# Computation.net
KiCad netlist of a schematic drawn in Altium Designer
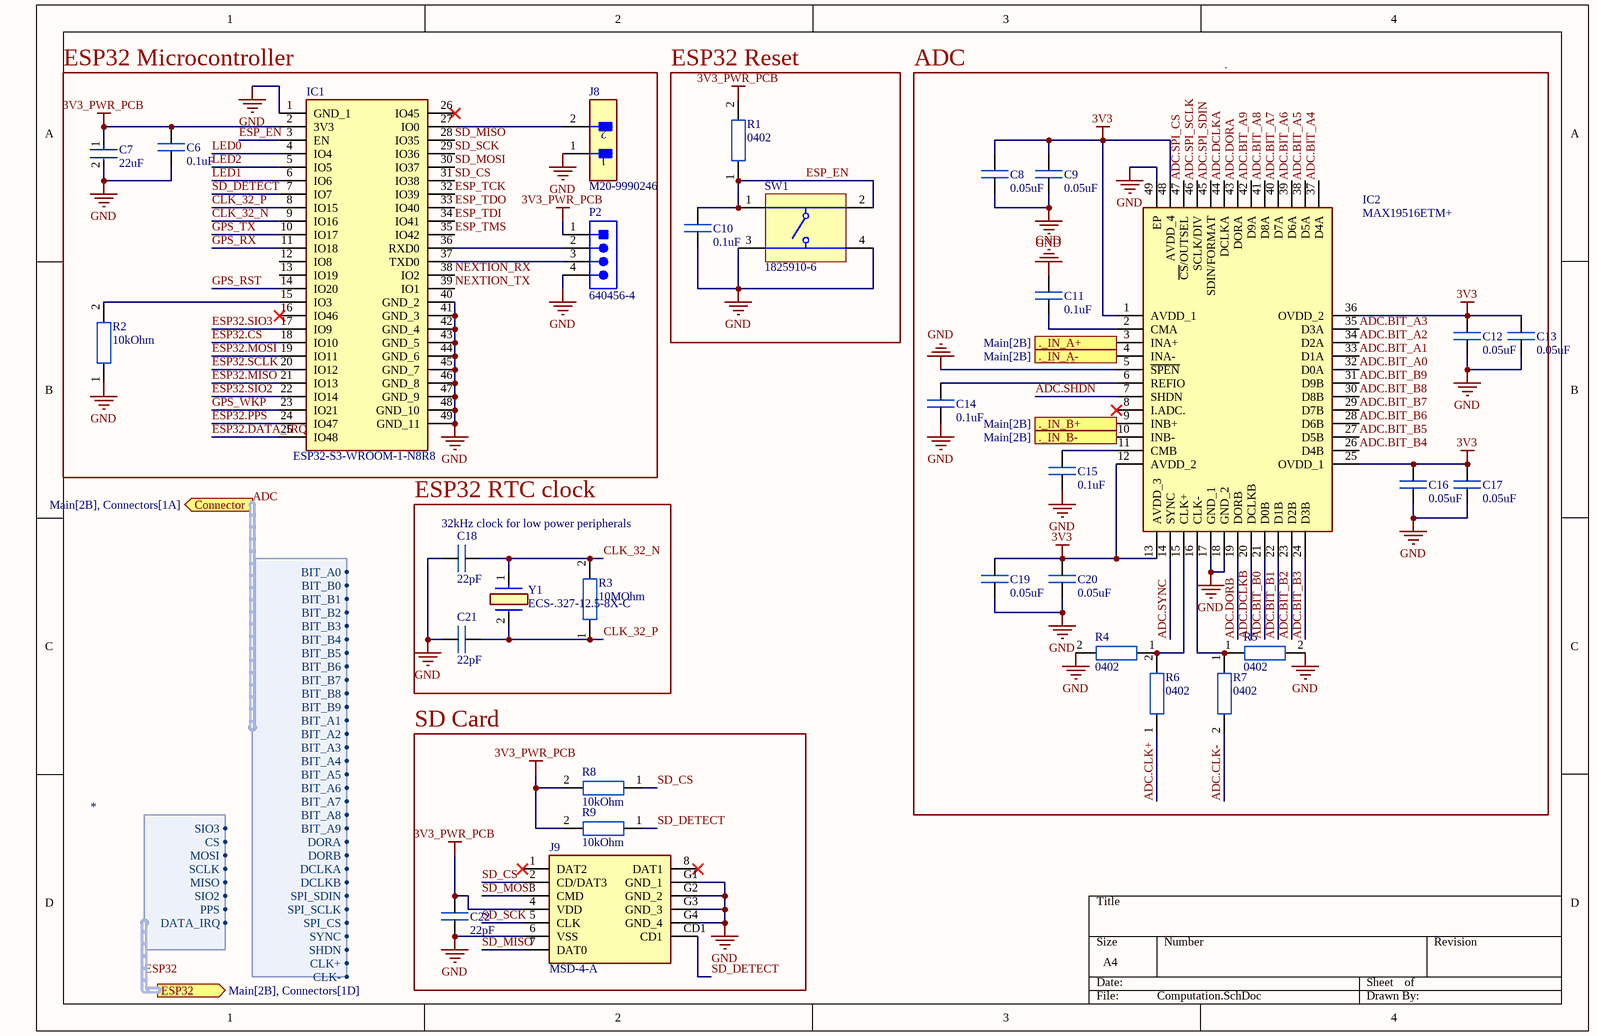
[diagram p0: Computation.SchDoc]

(export (version "E")
  (design (tool "Eeschema 10.0.6"))
  (components
    (comp (ref "C6")
      (value "0.1uF")
      (footprint "0402_footprint")
      (description "0402 capacitor")
      (libsource (lib "Schlib1") (part "Capacitor_0402"))
    )
    (comp (ref "C7")
      (value "22uF")
      (footprint "FP-CL21-IPC_B")
      (description "CL21 Series 0805 22uF 6.3V ±20% Tolerance X5R Multilayer Ceramic Chip Capacitor")
      (fields (field (name "TOLERANCE") "20%"))
      (libsource (lib "Altium Content Vault") (part "b4654b650e69147ec39a6b967a45e02"))
    )
    (comp (ref "C8")
      (value "0.05uF")
      (footprint "0402_footprint")
      (description "0402 capacitor")
      (libsource (lib "Schlib1") (part "Capacitor_0402"))
    )
    (comp (ref "C9")
      (value "0.05uF")
      (footprint "0402_footprint")
      (description "0402 capacitor")
      (libsource (lib "Schlib1") (part "Capacitor_0402"))
    )
    (comp (ref "C10")
      (value "0.1uF")
      (footprint "0402_footprint")
      (description "0402 capacitor")
      (libsource (lib "Schlib1") (part "Capacitor_0402"))
    )
    (comp (ref "C11")
      (value "0.1uF")
      (footprint "0402_footprint")
      (description "0402 capacitor")
      (libsource (lib "Schlib1") (part "Capacitor_0402"))
    )
    (comp (ref "C12")
      (value "0.05uF")
      (footprint "0402_footprint")
      (description "0402 capacitor")
      (libsource (lib "Schlib1") (part "Capacitor_0402"))
    )
    (comp (ref "C13")
      (value "0.05uF")
      (footprint "0402_footprint")
      (description "0402 capacitor")
      (libsource (lib "Schlib1") (part "Capacitor_0402"))
    )
    (comp (ref "C14")
      (value "0.1uF")
      (footprint "0402_footprint")
      (description "0402 capacitor")
      (libsource (lib "Schlib1") (part "Capacitor_0402"))
    )
    (comp (ref "C15")
      (value "0.1uF")
      (footprint "0402_footprint")
      (description "0402 capacitor")
      (libsource (lib "Schlib1") (part "Capacitor_0402"))
    )
    (comp (ref "C16")
      (value "0.05uF")
      (footprint "0402_footprint")
      (description "0402 capacitor")
      (libsource (lib "Schlib1") (part "Capacitor_0402"))
    )
    (comp (ref "C17")
      (value "0.05uF")
      (footprint "0402_footprint")
      (description "0402 capacitor")
      (libsource (lib "Schlib1") (part "Capacitor_0402"))
    )
    (comp (ref "C18")
      (value "22pF")
      (footprint "0402_footprint")
      (description "0402 capacitor")
      (libsource (lib "Schlib1") (part "Capacitor_0402"))
    )
    (comp (ref "C19")
      (value "0.05uF")
      (footprint "0402_footprint")
      (description "0402 capacitor")
      (libsource (lib "Schlib1") (part "Capacitor_0402"))
    )
    (comp (ref "C20")
      (value "0.05uF")
      (footprint "0402_footprint")
      (description "0402 capacitor")
      (libsource (lib "Schlib1") (part "Capacitor_0402"))
    )
    (comp (ref "C21")
      (value "22pF")
      (footprint "0402_footprint")
      (description "0402 capacitor")
      (libsource (lib "Schlib1") (part "Capacitor_0402"))
    )
    (comp (ref "C22")
      (value "22pF")
      (footprint "0402_footprint")
      (description "0402 capacitor")
      (libsource (lib "Schlib1") (part "Capacitor_0402"))
    )
    (comp (ref "IC1")
      (value "ESP32-S3-WROOM-1-N8R8")
      (footprint "SamacSys:ESP32S3WROOM1N8R8")
      (description "Integrated Circuit")
      (fields (field (name "MOUSER PART NUMBER") "356-EP32S3WROOM1N8R8"))
      (libsource (lib "*") (part "ESP32-S3-WROOM-1-N8R8"))
    )
    (comp (ref "IC2")
      (value "MAX19516ETM+")
      (footprint "SamacSys:QFN50P700X700X80-49N")
      (description "Integrated Circuit")
      (fields (field (name "MOUSER PART NUMBER") "700-MAX19516ETM"))
      (libsource (lib "*") (part "MAX19516ETM+"))
    )
    (comp (ref "J8")
      (value "M20-9990246")
      (footprint "FP-M20-9990246-MFG")
      (description "CONN HEADER VERT 2POS 2.54MM")
      (fields
        (field (name "OCTOPART") "https://octopart.com/m20-9990246-harwin-2590635")
        (field (name "MANUFACTURER") "Harwin")
      )
      (libsource (lib "Altium Content Vault") (part "3bc925449376181038e59eaffc5286c"))
    )
    (comp (ref "J9")
      (value "MSD-4-A")
      (footprint "SamacSys:MSD4A")
      (description "Connector")
      (libsource (lib "*") (part "MSD-4-A"))
    )
    (comp (ref "P2")
      (value "640456-4")
      (footprint "TECO-640456-4")
      (description "Male Header, Pitch 2.54 mm, 1 x 4 Position, Height 10.03 mm, Tail Length 3.56 mm, RoHS, Bulk")
      (fields (field (name "MANUFACTURER") "TE Connectivity"))
      (libsource (lib "Altium Content Vault") (part "CN-1P-M-R4"))
    )
    (comp (ref "R1")
      (value "0402")
      (footprint "0402_footprint")
      (description "0402 resistor")
      (libsource (lib "Schlib1") (part "Resistor_0402"))
    )
    (comp (ref "R2")
      (value "10kOhm")
      (footprint "0402_footprint")
      (description "0402 resistor")
      (libsource (lib "Schlib1") (part "Resistor_0402"))
    )
    (comp (ref "R3")
      (value "10MOhm")
      (footprint "0402_footprint")
      (description "0402 resistor")
      (libsource (lib "Schlib1") (part "Resistor_0402"))
    )
    (comp (ref "R4")
      (value "0402")
      (footprint "0402_footprint")
      (description "0402 resistor")
      (libsource (lib "Schlib1") (part "Resistor_0402"))
    )
    (comp (ref "R5")
      (value "0402")
      (footprint "0402_footprint")
      (description "0402 resistor")
      (libsource (lib "Schlib1") (part "Resistor_0402"))
    )
    (comp (ref "R6")
      (value "0402")
      (footprint "0402_footprint")
      (description "0402 resistor")
      (libsource (lib "Schlib1") (part "Resistor_0402"))
    )
    (comp (ref "R7")
      (value "0402")
      (footprint "0402_footprint")
      (description "0402 resistor")
      (libsource (lib "Schlib1") (part "Resistor_0402"))
    )
    (comp (ref "R8")
      (value "10kOhm")
      (footprint "0402_footprint")
      (description "0402 resistor")
      (libsource (lib "Schlib1") (part "Resistor_0402"))
    )
    (comp (ref "R9")
      (value "10kOhm")
      (footprint "0402_footprint")
      (description "0402 resistor")
      (libsource (lib "Schlib1") (part "Resistor_0402"))
    )
    (comp (ref "SW1")
      (value "1825910-6")
      (footprint "TECO-1825910-6_V")
      (description "Tact Switch, SPST-NO, 0.05 A, -35 to 85 degC, 4-Pin THD, RoHS, Bulk")
      (fields (field (name "MANUFACTURER") "TE Connectivity"))
      (libsource (lib "Altium Content Vault") (part "SW-SPST-4_A"))
    )
    (comp (ref "Y1")
      (value "ECS-.327-12.5-8X-C")
      (footprint "SamacSys:ECS3271258XC")
      (description "Crystal or Oscillator")
      (fields (field (name "MOUSER PART NUMBER") "520-ECS-327-12.58X-C"))
      (libsource (lib "*") (part "ECS-.327-12.5-8X-C"))
    )
  )
  (nets
    (net (code "3") (name "/._IN_A+") (class "Default")
      (node (ref "IC2") (pin "3") (pinfunction "INA+_3") (pintype "passive"))
    )
    (net (code "4") (name "/._IN_A-") (class "Default")
      (node (ref "IC2") (pin "4") (pinfunction "INA-_4") (pintype "passive"))
    )
    (net (code "5") (name "/._IN_B+") (class "Default")
      (node (ref "IC2") (pin "9") (pinfunction "INB+_9") (pintype "passive"))
    )
    (net (code "6") (name "/._IN_B-") (class "Default")
      (node (ref "IC2") (pin "10") (pinfunction "INB-_10") (pintype "passive"))
    )
    (net (code "7") (name "/ADC.BIT_A0") (class "Default")
      (node (ref "IC2") (pin "32") (pinfunction "D0A_32") (pintype "passive"))
    )
    (net (code "8") (name "/ADC.BIT_A1") (class "Default")
      (node (ref "IC2") (pin "33") (pinfunction "D1A_33") (pintype "passive"))
    )
    (net (code "9") (name "/ADC.BIT_A2") (class "Default")
      (node (ref "IC2") (pin "34") (pinfunction "D2A_34") (pintype "passive"))
    )
    (net (code "10") (name "/ADC.BIT_A3") (class "Default")
      (node (ref "IC2") (pin "35") (pinfunction "D3A_35") (pintype "passive"))
    )
    (net (code "11") (name "/ADC.BIT_A4") (class "Default")
      (node (ref "IC2") (pin "37") (pinfunction "D4A_37") (pintype "passive"))
    )
    (net (code "12") (name "/ADC.BIT_A5") (class "Default")
      (node (ref "IC2") (pin "38") (pinfunction "D5A_38") (pintype "passive"))
    )
    (net (code "13") (name "/ADC.BIT_A6") (class "Default")
      (node (ref "IC2") (pin "39") (pinfunction "D6A_39") (pintype "passive"))
    )
    (net (code "14") (name "/ADC.BIT_A7") (class "Default")
      (node (ref "IC2") (pin "40") (pinfunction "D7A_40") (pintype "passive"))
    )
    (net (code "15") (name "/ADC.BIT_A8") (class "Default")
      (node (ref "IC2") (pin "41") (pinfunction "D8A_41") (pintype "passive"))
    )
    (net (code "16") (name "/ADC.BIT_A9") (class "Default")
      (node (ref "IC2") (pin "42") (pinfunction "D9A_42") (pintype "passive"))
    )
    (net (code "17") (name "/ADC.BIT_B0") (class "Default")
      (node (ref "IC2") (pin "21") (pinfunction "D0B_21") (pintype "passive"))
    )
    (net (code "18") (name "/ADC.BIT_B1") (class "Default")
      (node (ref "IC2") (pin "22") (pinfunction "D1B_22") (pintype "passive"))
    )
    (net (code "19") (name "/ADC.BIT_B2") (class "Default")
      (node (ref "IC2") (pin "23") (pinfunction "D2B_23") (pintype "passive"))
    )
    (net (code "20") (name "/ADC.BIT_B3") (class "Default")
      (node (ref "IC2") (pin "24") (pinfunction "D3B_24") (pintype "passive"))
    )
    (net (code "21") (name "/ADC.BIT_B4") (class "Default")
      (node (ref "IC2") (pin "26") (pinfunction "D4B_26") (pintype "passive"))
    )
    (net (code "22") (name "/ADC.BIT_B5") (class "Default")
      (node (ref "IC2") (pin "27") (pinfunction "D5B_27") (pintype "passive"))
    )
    (net (code "23") (name "/ADC.BIT_B6") (class "Default")
      (node (ref "IC2") (pin "28") (pinfunction "D6B_28") (pintype "passive"))
    )
    (net (code "24") (name "/ADC.BIT_B7") (class "Default")
      (node (ref "IC2") (pin "29") (pinfunction "D7B_29") (pintype "passive"))
    )
    (net (code "25") (name "/ADC.BIT_B8") (class "Default")
      (node (ref "IC2") (pin "30") (pinfunction "D8B_30") (pintype "passive"))
    )
    (net (code "26") (name "/ADC.BIT_B9") (class "Default")
      (node (ref "IC2") (pin "31") (pinfunction "D9B_31") (pintype "passive"))
    )
    (net (code "27") (name "/ADC.CLK+") (class "Default")
      (node (ref "R6") (pin "1") (pinfunction "1_1") (pintype "passive"))
    )
    (net (code "28") (name "/ADC.CLK-") (class "Default")
      (node (ref "R7") (pin "2") (pinfunction "2_2") (pintype "passive"))
    )
    (net (code "29") (name "/ADC.DCLKA") (class "Default")
      (node (ref "IC2") (pin "44") (pinfunction "DCLKA_44") (pintype "passive"))
    )
    (net (code "30") (name "/ADC.DCLKB") (class "Default")
      (node (ref "IC2") (pin "20") (pinfunction "DCLKB_20") (pintype "passive"))
    )
    (net (code "31") (name "/ADC.DORA") (class "Default")
      (node (ref "IC2") (pin "43") (pinfunction "DORA_43") (pintype "passive"))
    )
    (net (code "32") (name "/ADC.DORB") (class "Default")
      (node (ref "IC2") (pin "19") (pinfunction "DORB_19") (pintype "passive"))
    )
    (net (code "33") (name "/ADC.SHDN") (class "Default")
      (node (ref "IC2") (pin "7") (pinfunction "SHDN_7") (pintype "passive"))
    )
    (net (code "34") (name "/ADC.SPI_CS") (class "Default")
      (node (ref "IC2") (pin "47") (pinfunction "~{CS}/OUTSEL_47") (pintype "passive"))
    )
    (net (code "35") (name "/ADC.SPI_SCLK") (class "Default")
      (node (ref "IC2") (pin "46") (pinfunction "SCLK/DIV_46") (pintype "passive"))
    )
    (net (code "36") (name "/ADC.SPI_SDIN") (class "Default")
      (node (ref "IC2") (pin "45") (pinfunction "SDIN/FORMAT_45") (pintype "passive"))
    )
    (net (code "37") (name "/ADC.SYNC") (class "Default")
      (node (ref "IC2") (pin "14") (pinfunction "SYNC_14") (pintype "passive"))
    )
    (net (code "39") (name "/CLK_32_N") (class "Default")
      (node (ref "C18") (pin "1") (pinfunction "1_1") (pintype "passive"))
      (node (ref "IC1") (pin "9") (pinfunction "IO16_9") (pintype "passive"))
      (node (ref "R3") (pin "2") (pinfunction "2_2") (pintype "passive"))
      (node (ref "Y1") (pin "1") (pinfunction "X1_1") (pintype "passive"))
    )
    (net (code "40") (name "/CLK_32_P") (class "Default")
      (node (ref "C21") (pin "1") (pinfunction "1_1") (pintype "passive"))
      (node (ref "IC1") (pin "8") (pinfunction "IO15_8") (pintype "passive"))
      (node (ref "R3") (pin "1") (pinfunction "1_1") (pintype "passive"))
      (node (ref "Y1") (pin "2") (pinfunction "X2_2") (pintype "passive"))
    )
    (net (code "41") (name "/ESP32.CS") (class "Default")
      (node (ref "IC1") (pin "18") (pinfunction "IO10_18") (pintype "passive"))
    )
    (net (code "42") (name "/ESP32.DATA_IRQ") (class "Default")
      (node (ref "IC1") (pin "25") (pinfunction "IO48_25") (pintype "passive"))
    )
    (net (code "43") (name "/ESP32.MISO") (class "Default")
      (node (ref "IC1") (pin "21") (pinfunction "IO13_21") (pintype "passive"))
    )
    (net (code "44") (name "/ESP32.MOSI") (class "Default")
      (node (ref "IC1") (pin "19") (pinfunction "IO11_19") (pintype "passive"))
    )
    (net (code "45") (name "/ESP32.PPS") (class "Default")
      (node (ref "IC1") (pin "24") (pinfunction "IO47_24") (pintype "passive"))
    )
    (net (code "46") (name "/ESP32.SCLK") (class "Default")
      (node (ref "IC1") (pin "20") (pinfunction "IO12_20") (pintype "passive"))
    )
    (net (code "47") (name "/ESP32.SIO2") (class "Default")
      (node (ref "IC1") (pin "22") (pinfunction "IO14_22") (pintype "passive"))
    )
    (net (code "48") (name "/ESP32.SIO3") (class "Default")
      (node (ref "IC1") (pin "17") (pinfunction "IO9_17") (pintype "passive"))
    )
    (net (code "50") (name "/ESP_EN") (class "Default")
      (node (ref "C10") (pin "2") (pinfunction "2_2") (pintype "passive"))
      (node (ref "IC1") (pin "3") (pinfunction "EN_3") (pintype "passive"))
      (node (ref "R1") (pin "1") (pinfunction "1_1") (pintype "passive"))
      (node (ref "SW1") (pin "1") (pinfunction "1_1") (pintype "passive"))
      (node (ref "SW1") (pin "2") (pinfunction "2_2") (pintype "passive"))
    )
    (net (code "51") (name "/ESP_TCK") (class "Default")
      (node (ref "IC1") (pin "32") (pinfunction "IO39_32") (pintype "passive"))
    )
    (net (code "52") (name "/ESP_TDI") (class "Default")
      (node (ref "IC1") (pin "34") (pinfunction "IO41_34") (pintype "passive"))
    )
    (net (code "53") (name "/ESP_TDO") (class "Default")
      (node (ref "IC1") (pin "33") (pinfunction "IO40_33") (pintype "passive"))
    )
    (net (code "54") (name "/ESP_TMS") (class "Default")
      (node (ref "IC1") (pin "35") (pinfunction "IO42_35") (pintype "passive"))
    )
    (net (code "55") (name "/GPS_RST") (class "Default")
      (node (ref "IC1") (pin "14") (pinfunction "IO20_14") (pintype "passive"))
    )
    (net (code "56") (name "/GPS_RX") (class "Default")
      (node (ref "IC1") (pin "11") (pinfunction "IO18_11") (pintype "passive"))
    )
    (net (code "57") (name "/GPS_TX") (class "Default")
      (node (ref "IC1") (pin "10") (pinfunction "IO17_10") (pintype "passive"))
    )
    (net (code "58") (name "/GPS_WKP") (class "Default")
      (node (ref "IC1") (pin "23") (pinfunction "IO21_23") (pintype "passive"))
    )
    (net (code "59") (name "/LED0") (class "Default")
      (node (ref "IC1") (pin "4") (pinfunction "IO4_4") (pintype "passive"))
    )
    (net (code "60") (name "/LED1") (class "Default")
      (node (ref "IC1") (pin "6") (pinfunction "IO6_6") (pintype "passive"))
    )
    (net (code "61") (name "/LED2") (class "Default")
      (node (ref "IC1") (pin "5") (pinfunction "IO5_5") (pintype "passive"))
    )
    (net (code "62") (name "/NEXTION_RX") (class "Default")
      (node (ref "IC1") (pin "38") (pinfunction "IO2_38") (pintype "passive"))
    )
    (net (code "63") (name "/NEXTION_TX") (class "Default")
      (node (ref "IC1") (pin "39") (pinfunction "IO1_39") (pintype "passive"))
    )
    (net (code "64") (name "/SD_CS") (class "Default")
      (node (ref "IC1") (pin "31") (pinfunction "IO38_31") (pintype "passive"))
      (node (ref "J9") (pin "2") (pinfunction "CD/DAT3_2") (pintype "passive"))
      (node (ref "R8") (pin "1") (pinfunction "1_1") (pintype "passive"))
    )
    (net (code "65") (name "/SD_DETECT") (class "Default")
      (node (ref "IC1") (pin "7") (pinfunction "IO7_7") (pintype "passive"))
      (node (ref "J9") (pin "CD1") (pinfunction "CD1_CD1") (pintype "passive"))
      (node (ref "R9") (pin "1") (pinfunction "1_1") (pintype "passive"))
    )
    (net (code "66") (name "/SD_MISO") (class "Default")
      (node (ref "IC1") (pin "28") (pinfunction "IO35_28") (pintype "passive"))
      (node (ref "J9") (pin "7") (pinfunction "DAT0_7") (pintype "passive"))
    )
    (net (code "67") (name "/SD_MOSI") (class "Default")
      (node (ref "IC1") (pin "30") (pinfunction "IO37_30") (pintype "passive"))
      (node (ref "J9") (pin "3") (pinfunction "CMD_3") (pintype "passive"))
    )
    (net (code "68") (name "/SD_SCK") (class "Default")
      (node (ref "IC1") (pin "29") (pinfunction "IO36_29") (pintype "passive"))
      (node (ref "J9") (pin "5") (pinfunction "CLK_5") (pintype "passive"))
    )
    (net (code "69") (name "3V3") (class "Default")
      (node (ref "C12") (pin "2") (pinfunction "2_2") (pintype "passive"))
      (node (ref "C13") (pin "2") (pinfunction "2_2") (pintype "passive"))
      (node (ref "C16") (pin "2") (pinfunction "2_2") (pintype "passive"))
      (node (ref "C17") (pin "2") (pinfunction "2_2") (pintype "passive"))
      (node (ref "C19") (pin "2") (pinfunction "2_2") (pintype "passive"))
      (node (ref "C20") (pin "2") (pinfunction "2_2") (pintype "passive"))
      (node (ref "C8") (pin "2") (pinfunction "2_2") (pintype "passive"))
      (node (ref "C9") (pin "2") (pinfunction "2_2") (pintype "passive"))
      (node (ref "IC2") (pin "1") (pinfunction "AVDD_1_1") (pintype "passive"))
      (node (ref "IC2") (pin "12") (pinfunction "AVDD_2_12") (pintype "passive"))
      (node (ref "IC2") (pin "13") (pinfunction "AVDD_3_13") (pintype "passive"))
      (node (ref "IC2") (pin "25") (pinfunction "OVDD_1_25") (pintype "passive"))
      (node (ref "IC2") (pin "36") (pinfunction "OVDD_2_36") (pintype "passive"))
      (node (ref "IC2") (pin "48") (pinfunction "AVDD_4_48") (pintype "passive"))
    )
    (net (code "70") (name "3V3_PWR_PCB") (class "Default")
      (node (ref "C22") (pin "1") (pinfunction "1_1") (pintype "passive"))
      (node (ref "C6") (pin "2") (pinfunction "2_2") (pintype "passive"))
      (node (ref "C7") (pin "1") (pinfunction "1_1") (pintype "passive"))
      (node (ref "IC1") (pin "2") (pinfunction "3V3_2") (pintype "passive"))
      (node (ref "J9") (pin "4") (pinfunction "VDD_4") (pintype "passive"))
      (node (ref "P2") (pin "1") (pinfunction "1_1") (pintype "passive"))
      (node (ref "R1") (pin "2") (pinfunction "2_2") (pintype "passive"))
      (node (ref "R8") (pin "2") (pinfunction "2_2") (pintype "passive"))
      (node (ref "R9") (pin "2") (pinfunction "2_2") (pintype "passive"))
    )
    (net (code "71") (name "GND") (class "Default")
      (node (ref "C10") (pin "1") (pinfunction "1_1") (pintype "passive"))
      (node (ref "C11") (pin "2") (pinfunction "2_2") (pintype "passive"))
      (node (ref "C12") (pin "1") (pinfunction "1_1") (pintype "passive"))
      (node (ref "C13") (pin "1") (pinfunction "1_1") (pintype "passive"))
      (node (ref "C14") (pin "1") (pinfunction "1_1") (pintype "passive"))
      (node (ref "C15") (pin "1") (pinfunction "1_1") (pintype "passive"))
      (node (ref "C16") (pin "1") (pinfunction "1_1") (pintype "passive"))
      (node (ref "C17") (pin "1") (pinfunction "1_1") (pintype "passive"))
      (node (ref "C18") (pin "2") (pinfunction "2_2") (pintype "passive"))
      (node (ref "C19") (pin "1") (pinfunction "1_1") (pintype "passive"))
      (node (ref "C20") (pin "1") (pinfunction "1_1") (pintype "passive"))
      (node (ref "C21") (pin "2") (pinfunction "2_2") (pintype "passive"))
      (node (ref "C22") (pin "2") (pinfunction "2_2") (pintype "passive"))
      (node (ref "C6") (pin "1") (pinfunction "1_1") (pintype "passive"))
      (node (ref "C7") (pin "2") (pinfunction "2_2") (pintype "passive"))
      (node (ref "C8") (pin "1") (pinfunction "1_1") (pintype "passive"))
      (node (ref "C9") (pin "1") (pinfunction "1_1") (pintype "passive"))
      (node (ref "IC1") (pin "1") (pinfunction "GND_1_1") (pintype "passive"))
      (node (ref "IC1") (pin "40") (pinfunction "GND_2_40") (pintype "passive"))
      (node (ref "IC1") (pin "41") (pinfunction "GND_3_41") (pintype "passive"))
      (node (ref "IC1") (pin "42") (pinfunction "GND_4_42") (pintype "passive"))
      (node (ref "IC1") (pin "43") (pinfunction "GND_5_43") (pintype "passive"))
      (node (ref "IC1") (pin "44") (pinfunction "GND_6_44") (pintype "passive"))
      (node (ref "IC1") (pin "45") (pinfunction "GND_7_45") (pintype "passive"))
      (node (ref "IC1") (pin "46") (pinfunction "GND_8_46") (pintype "passive"))
      (node (ref "IC1") (pin "47") (pinfunction "GND_9_47") (pintype "passive"))
      (node (ref "IC1") (pin "48") (pinfunction "GND_10_48") (pintype "passive"))
      (node (ref "IC1") (pin "49") (pinfunction "GND_11_49") (pintype "passive"))
      (node (ref "IC2") (pin "17") (pinfunction "GND_1_17") (pintype "passive"))
      (node (ref "IC2") (pin "18") (pinfunction "GND_2_18") (pintype "passive"))
      (node (ref "IC2") (pin "49") (pinfunction "EP_49") (pintype "passive"))
      (node (ref "IC2") (pin "5") (pinfunction "~{SPEN}_5") (pintype "passive"))
      (node (ref "J8") (pin "1") (pinfunction "1_1") (pintype "passive"))
      (node (ref "J9") (pin "6") (pinfunction "VSS_6") (pintype "passive"))
      (node (ref "J9") (pin "G1") (pinfunction "GND_1_G1") (pintype "passive"))
      (node (ref "J9") (pin "G2") (pinfunction "GND_2_G2") (pintype "passive"))
      (node (ref "J9") (pin "G3") (pinfunction "GND_3_G3") (pintype "passive"))
      (node (ref "J9") (pin "G4") (pinfunction "GND_4_G4") (pintype "passive"))
      (node (ref "P2") (pin "4") (pinfunction "4_4") (pintype "passive"))
      (node (ref "R2") (pin "1") (pinfunction "1_1") (pintype "passive"))
      (node (ref "R4") (pin "2") (pinfunction "2_2") (pintype "passive"))
      (node (ref "R5") (pin "2") (pinfunction "2_2") (pintype "passive"))
      (node (ref "SW1") (pin "3") (pinfunction "3_3") (pintype "passive"))
      (node (ref "SW1") (pin "4") (pinfunction "4_4") (pintype "passive"))
    )
    (net (code "72") (name "Net-(IC1-IO0)") (class "Default")
      (node (ref "IC1") (pin "27") (pinfunction "IO0_27") (pintype "passive"))
      (node (ref "J8") (pin "2") (pinfunction "2_2") (pintype "passive"))
    )
    (net (code "73") (name "Net-(IC1-IO3)") (class "Default")
      (node (ref "IC1") (pin "15") (pinfunction "IO3_15") (pintype "passive"))
      (node (ref "R2") (pin "2") (pinfunction "2_2") (pintype "passive"))
    )
    (net (code "74") (name "Net-(IC1-RXD0)") (class "Default")
      (node (ref "IC1") (pin "36") (pinfunction "RXD0_36") (pintype "passive"))
      (node (ref "P2") (pin "2") (pinfunction "2_2") (pintype "passive"))
    )
    (net (code "75") (name "Net-(IC1-TXD0)") (class "Default")
      (node (ref "IC1") (pin "37") (pinfunction "TXD0_37") (pintype "passive"))
      (node (ref "P2") (pin "3") (pinfunction "3_3") (pintype "passive"))
    )
    (net (code "76") (name "Net-(IC2-CLK+)") (class "Default")
      (node (ref "IC2") (pin "15") (pinfunction "CLK+_15") (pintype "passive"))
      (node (ref "R4") (pin "1") (pinfunction "1_1") (pintype "passive"))
      (node (ref "R6") (pin "2") (pinfunction "2_2") (pintype "passive"))
    )
    (net (code "77") (name "Net-(IC2-CLK-)") (class "Default")
      (node (ref "IC2") (pin "16") (pinfunction "CLK-_16") (pintype "passive"))
      (node (ref "R5") (pin "1") (pinfunction "1_1") (pintype "passive"))
      (node (ref "R7") (pin "1") (pinfunction "1_1") (pintype "passive"))
    )
    (net (code "78") (name "Net-(IC2-CMA)") (class "Default")
      (node (ref "C11") (pin "1") (pinfunction "1_1") (pintype "passive"))
      (node (ref "IC2") (pin "2") (pinfunction "CMA_2") (pintype "passive"))
    )
    (net (code "79") (name "Net-(IC2-CMB)") (class "Default")
      (node (ref "C15") (pin "2") (pinfunction "2_2") (pintype "passive"))
      (node (ref "IC2") (pin "11") (pinfunction "CMB_11") (pintype "passive"))
    )
    (net (code "80") (name "Net-(IC2-REFIO)") (class "Default")
      (node (ref "C14") (pin "2") (pinfunction "2_2") (pintype "passive"))
      (node (ref "IC2") (pin "6") (pinfunction "REFIO_6") (pintype "passive"))
    )
    (net (code "81") (name "unconnected-(IC1-IO8-Pad12)") (class "Default")
      (node (ref "IC1") (pin "12") (pinfunction "IO8_12") (pintype "passive"))
    )
    (net (code "82") (name "unconnected-(IC1-IO19-Pad13)") (class "Default")
      (node (ref "IC1") (pin "13") (pinfunction "IO19_13") (pintype "passive"))
    )
    (net (code "83") (name "unconnected-(IC1-IO45-Pad26)") (class "Default")
      (node (ref "IC1") (pin "26") (pinfunction "IO45_26") (pintype "passive+no_connect"))
    )
    (net (code "84") (name "unconnected-(IC1-IO46-Pad16)") (class "Default")
      (node (ref "IC1") (pin "16") (pinfunction "IO46_16") (pintype "passive+no_connect"))
    )
    (net (code "85") (name "unconnected-(IC2-I.ADC.-Pad8)") (class "Default")
      (node (ref "IC2") (pin "8") (pinfunction "I.ADC._8") (pintype "passive+no_connect"))
    )
    (net (code "86") (name "unconnected-(J9-DAT1-Pad8)") (class "Default")
      (node (ref "J9") (pin "8") (pinfunction "DAT1_8") (pintype "passive+no_connect"))
    )
    (net (code "87") (name "unconnected-(J9-DAT2-Pad1)") (class "Default")
      (node (ref "J9") (pin "1") (pinfunction "DAT2_1") (pintype "passive+no_connect"))
    )
  )
)
